# modul_procesora.net
KiCad netlist of a schematic drawn in EAGLE
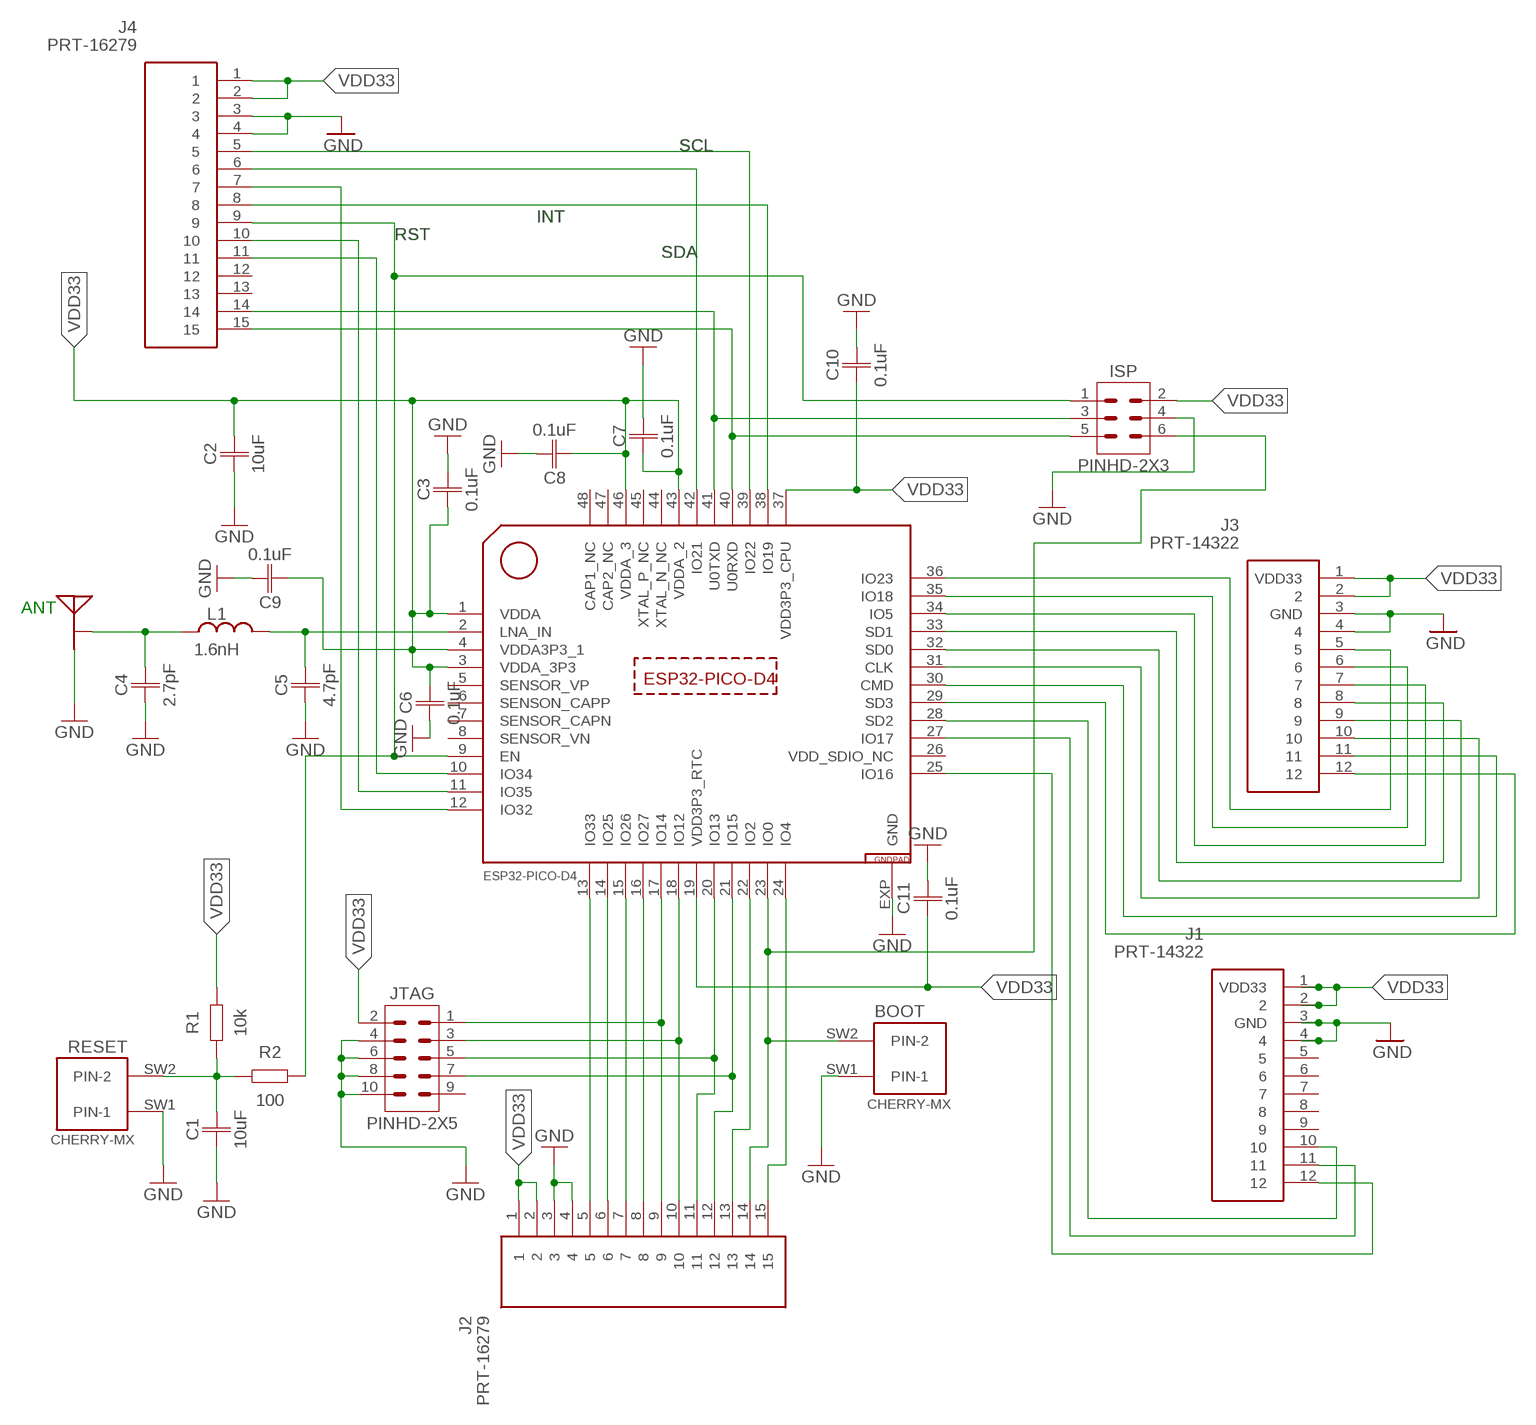
[diagram p0: schematic, sheet 1]

(export (version "E")
  (design (tool "Eeschema 10.0.6"))
  (components
    (comp (ref "ANT")
      (value "ANT")
      (footprint "eagle-import:MEANDER-ANT")
      (libsource (lib "eagle-import") (part "MEANDER-ANT"))
    )
    (comp (ref "BOOT")
      (value "BOOT")
      (footprint "eagle-import:CHERRY-MX")
      (libsource (lib "eagle-import") (part "CHERRY-MX"))
    )
    (comp (ref "C1")
      (value "10uF")
      (footprint "eagle-import:CAPC1005X60")
      (libsource (lib "eagle-import") (part "CCHIP-0402(1005-METRIC)_"))
    )
    (comp (ref "C2")
      (value "10uF")
      (footprint "eagle-import:CAPC1005X60")
      (libsource (lib "eagle-import") (part "CCHIP-0402(1005-METRIC)_"))
    )
    (comp (ref "C3")
      (value "0.1uF")
      (footprint "eagle-import:CAPC1005X60")
      (libsource (lib "eagle-import") (part "CCHIP-0402(1005-METRIC)_"))
    )
    (comp (ref "C4")
      (value "2.7pF")
      (footprint "eagle-import:CAPC1005X60")
      (libsource (lib "eagle-import") (part "CCHIP-0402(1005-METRIC)_"))
    )
    (comp (ref "C5")
      (value "4.7pF")
      (footprint "eagle-import:CAPC1005X60")
      (libsource (lib "eagle-import") (part "CCHIP-0402(1005-METRIC)_"))
    )
    (comp (ref "C6")
      (value "0.1uF")
      (footprint "eagle-import:CAPC1005X60")
      (libsource (lib "eagle-import") (part "CCHIP-0402(1005-METRIC)_"))
    )
    (comp (ref "C7")
      (value "0.1uF")
      (footprint "eagle-import:CAPC1005X60")
      (libsource (lib "eagle-import") (part "CCHIP-0402(1005-METRIC)_"))
    )
    (comp (ref "C8")
      (value "0.1uF")
      (footprint "eagle-import:CAPC1005X60")
      (libsource (lib "eagle-import") (part "CCHIP-0402(1005-METRIC)_"))
    )
    (comp (ref "C9")
      (value "0.1uF")
      (footprint "eagle-import:CAPC1005X60")
      (libsource (lib "eagle-import") (part "CCHIP-0402(1005-METRIC)_"))
    )
    (comp (ref "C10")
      (value "0.1uF")
      (footprint "eagle-import:CAPC1005X60")
      (libsource (lib "eagle-import") (part "CCHIP-0402(1005-METRIC)_"))
    )
    (comp (ref "C11")
      (value "0.1uF")
      (footprint "eagle-import:CAPC1005X60")
      (libsource (lib "eagle-import") (part "CCHIP-0402(1005-METRIC)_"))
    )
    (comp (ref "ISP")
      (value "PINHD-2X3")
      (footprint "eagle-import:2X03")
      (libsource (lib "eagle-import") (part "PINHD-2X3"))
    )
    (comp (ref "J1")
      (value "PRT-14322")
      (footprint "eagle-import:RHDR12W87P0X254_1X12_3103X250X")
      (fields (field (name "MOUSER_PART_NUMBER") "474-PRT-14322"))
      (libsource (lib "eagle-import") (part "PRT-14322"))
    )
    (comp (ref "J2")
      (value "PRT-16279")
      (footprint "eagle-import:PRT16279")
      (fields (field (name "MOUSER_PART_NUMBER") "474-PRT-16279"))
      (libsource (lib "eagle-import") (part "PRT-16279"))
    )
    (comp (ref "J3")
      (value "PRT-14322")
      (footprint "eagle-import:RHDR12W87P0X254_1X12_3103X250X")
      (fields (field (name "MOUSER_PART_NUMBER") "474-PRT-14322"))
      (libsource (lib "eagle-import") (part "PRT-14322"))
    )
    (comp (ref "J4")
      (value "PRT-16279")
      (footprint "eagle-import:PRT16279")
      (fields (field (name "MOUSER_PART_NUMBER") "474-PRT-16279"))
      (libsource (lib "eagle-import") (part "PRT-16279"))
    )
    (comp (ref "JTAG")
      (value "PINHD-2X5")
      (footprint "eagle-import:2X05")
      (libsource (lib "eagle-import") (part "PINHD-2X5"))
    )
    (comp (ref "L1")
      (value "1.6nH")
      (footprint "eagle-import:INDC1006X60N")
      (libsource (lib "eagle-import") (part "INDUCTORCHIP-0402(1006-METRIC)_"))
    )
    (comp (ref "R1")
      (value "10k")
      (footprint "eagle-import:RESC1005X40")
      (libsource (lib "eagle-import") (part "RCHIP-0402(1005-METRIC)_"))
    )
    (comp (ref "R2")
      (value "100")
      (footprint "eagle-import:RESC1005X40")
      (libsource (lib "eagle-import") (part "RCHIP-0402(1005-METRIC)_"))
    )
    (comp (ref "RESET")
      (value "CHERRY-MX")
      (footprint "eagle-import:CHERRY-MX")
      (libsource (lib "eagle-import") (part "CHERRY-MX"))
    )
    (comp (ref "U$1")
      (value "ESP32-PICO-D4")
      (footprint "eagle-import:QFN48")
      (libsource (lib "eagle-import") (part "ESP32-PICO-D4"))
    )
  )
  (nets
    (net (code "1") (name "/INT") (class "Default")
      (node (ref "J4") (pin "8") (pinfunction "8_8") (pintype "bidirectional"))
      (node (ref "U$1") (pin "38") (pinfunction "IO19_38") (pintype "bidirectional"))
    )
    (net (code "2") (name "/RST") (class "Default")
      (node (ref "ISP") (pin "1") (pinfunction "1_1") (pintype "passive"))
      (node (ref "J4") (pin "9") (pinfunction "9_9") (pintype "bidirectional"))
      (node (ref "R2") (pin "2") (pinfunction "2_2") (pintype "passive"))
      (node (ref "U$1") (pin "9") (pinfunction "EN_9") (pintype "input"))
    )
    (net (code "3") (name "/SCL") (class "Default")
      (node (ref "J4") (pin "5") (pinfunction "5_5") (pintype "bidirectional"))
      (node (ref "U$1") (pin "39") (pinfunction "IO22_39") (pintype "bidirectional"))
    )
    (net (code "4") (name "/SDA") (class "Default")
      (node (ref "J4") (pin "6") (pinfunction "6_6") (pintype "bidirectional"))
      (node (ref "U$1") (pin "42") (pinfunction "IO21_42") (pintype "bidirectional"))
    )
    (net (code "5") (name "/VDD_SDIO_NC") (class "Default")
      (node (ref "U$1") (pin "26") (pinfunction "VDD_SDIO_NC_26") (pintype "power_in"))
    )
    (net (code "6") (name "GND") (class "Default")
      (node (ref "ANT") (pin "FEED") (pinfunction "FEED_FEED") (pintype "bidirectional"))
      (node (ref "BOOT") (pin "SW1") (pinfunction "PIN-1_SW1") (pintype "bidirectional"))
      (node (ref "C1") (pin "1") (pinfunction "1_1") (pintype "passive"))
      (node (ref "C10") (pin "2") (pinfunction "2_2") (pintype "passive"))
      (node (ref "C11") (pin "2") (pinfunction "2_2") (pintype "passive"))
      (node (ref "C2") (pin "1") (pinfunction "1_1") (pintype "passive"))
      (node (ref "C3") (pin "2") (pinfunction "2_2") (pintype "passive"))
      (node (ref "C4") (pin "1") (pinfunction "1_1") (pintype "passive"))
      (node (ref "C5") (pin "1") (pinfunction "1_1") (pintype "passive"))
      (node (ref "C6") (pin "1") (pinfunction "1_1") (pintype "passive"))
      (node (ref "C7") (pin "2") (pinfunction "2_2") (pintype "passive"))
      (node (ref "C8") (pin "2") (pinfunction "2_2") (pintype "passive"))
      (node (ref "C9") (pin "2") (pinfunction "2_2") (pintype "passive"))
      (node (ref "ISP") (pin "4") (pinfunction "4_4") (pintype "passive"))
      (node (ref "J1") (pin "3") (pinfunction "GND_3") (pintype "bidirectional"))
      (node (ref "J1") (pin "4") (pinfunction "4_4") (pintype "bidirectional"))
      (node (ref "J2") (pin "3") (pinfunction "3_3") (pintype "bidirectional"))
      (node (ref "J2") (pin "4") (pinfunction "4_4") (pintype "bidirectional"))
      (node (ref "J3") (pin "3") (pinfunction "GND_3") (pintype "bidirectional"))
      (node (ref "J3") (pin "4") (pinfunction "4_4") (pintype "bidirectional"))
      (node (ref "J4") (pin "3") (pinfunction "3_3") (pintype "bidirectional"))
      (node (ref "J4") (pin "4") (pinfunction "4_4") (pintype "bidirectional"))
      (node (ref "JTAG") (pin "10") (pinfunction "10_10") (pintype "passive"))
      (node (ref "JTAG") (pin "4") (pinfunction "4_4") (pintype "passive"))
      (node (ref "JTAG") (pin "6") (pinfunction "6_6") (pintype "passive"))
      (node (ref "JTAG") (pin "8") (pinfunction "8_8") (pintype "passive"))
      (node (ref "RESET") (pin "SW1") (pinfunction "PIN-1_SW1") (pintype "bidirectional"))
      (node (ref "U$1") (pin "EXP") (pinfunction "GND_EXP") (pintype "power_in"))
    )
    (net (code "7") (name "Net-(ANT-PadGND)") (class "Default")
      (node (ref "ANT") (pin "GND") (pinfunction "GND_GND") (pintype "bidirectional"))
      (node (ref "C4") (pin "2") (pinfunction "2_2") (pintype "passive"))
      (node (ref "L1") (pin "1") (pinfunction "1_1") (pintype "passive"))
    )
    (net (code "8") (name "Net-(BOOT-PIN-2)") (class "Default")
      (node (ref "BOOT") (pin "SW2") (pinfunction "PIN-2_SW2") (pintype "bidirectional"))
      (node (ref "ISP") (pin "6") (pinfunction "6_6") (pintype "passive"))
      (node (ref "J2") (pin "14") (pinfunction "14_14") (pintype "bidirectional"))
      (node (ref "U$1") (pin "23") (pinfunction "IO0_23") (pintype "bidirectional"))
    )
    (net (code "9") (name "Net-(RESET-PIN-2)") (class "Default")
      (node (ref "C1") (pin "2") (pinfunction "2_2") (pintype "passive"))
      (node (ref "R1") (pin "1") (pinfunction "1_1") (pintype "passive"))
      (node (ref "R2") (pin "1") (pinfunction "1_1") (pintype "passive"))
      (node (ref "RESET") (pin "SW2") (pinfunction "PIN-2_SW2") (pintype "bidirectional"))
    )
    (net (code "10") (name "Net-(U$1-CLK)") (class "Default")
      (node (ref "J3") (pin "10") (pinfunction "10_10") (pintype "bidirectional"))
      (node (ref "U$1") (pin "31") (pinfunction "CLK_31") (pintype "bidirectional"))
    )
    (net (code "11") (name "Net-(U$1-CMD)") (class "Default")
      (node (ref "J3") (pin "11") (pinfunction "11_11") (pintype "bidirectional"))
      (node (ref "U$1") (pin "30") (pinfunction "CMD_30") (pintype "bidirectional"))
    )
    (net (code "12") (name "Net-(U$1-IO2)") (class "Default")
      (node (ref "J2") (pin "13") (pinfunction "13_13") (pintype "bidirectional"))
      (node (ref "U$1") (pin "22") (pinfunction "IO2_22") (pintype "bidirectional"))
    )
    (net (code "13") (name "Net-(U$1-IO4)") (class "Default")
      (node (ref "J2") (pin "15") (pinfunction "15_15") (pintype "bidirectional"))
      (node (ref "U$1") (pin "24") (pinfunction "IO4_24") (pintype "bidirectional"))
    )
    (net (code "14") (name "Net-(U$1-IO5)") (class "Default")
      (node (ref "J3") (pin "7") (pinfunction "7_7") (pintype "bidirectional"))
      (node (ref "U$1") (pin "34") (pinfunction "IO5_34") (pintype "bidirectional"))
    )
    (net (code "15") (name "Net-(U$1-IO12)") (class "Default")
      (node (ref "J2") (pin "10") (pinfunction "10_10") (pintype "bidirectional"))
      (node (ref "JTAG") (pin "3") (pinfunction "3_3") (pintype "passive"))
      (node (ref "U$1") (pin "18") (pinfunction "IO12_18") (pintype "bidirectional"))
    )
    (net (code "16") (name "Net-(U$1-IO13)") (class "Default")
      (node (ref "J2") (pin "11") (pinfunction "11_11") (pintype "bidirectional"))
      (node (ref "JTAG") (pin "5") (pinfunction "5_5") (pintype "passive"))
      (node (ref "U$1") (pin "20") (pinfunction "IO13_20") (pintype "bidirectional"))
    )
    (net (code "17") (name "Net-(U$1-IO14)") (class "Default")
      (node (ref "J2") (pin "9") (pinfunction "9_9") (pintype "bidirectional"))
      (node (ref "JTAG") (pin "1") (pinfunction "1_1") (pintype "passive"))
      (node (ref "U$1") (pin "17") (pinfunction "IO14_17") (pintype "bidirectional"))
    )
    (net (code "18") (name "Net-(U$1-IO15)") (class "Default")
      (node (ref "J2") (pin "12") (pinfunction "12_12") (pintype "bidirectional"))
      (node (ref "JTAG") (pin "7") (pinfunction "7_7") (pintype "passive"))
      (node (ref "U$1") (pin "21") (pinfunction "IO15_21") (pintype "bidirectional"))
    )
    (net (code "19") (name "Net-(U$1-IO16)") (class "Default")
      (node (ref "J1") (pin "12") (pinfunction "12_12") (pintype "bidirectional"))
      (node (ref "U$1") (pin "25") (pinfunction "IO16_25") (pintype "bidirectional"))
    )
    (net (code "20") (name "Net-(U$1-IO17)") (class "Default")
      (node (ref "J1") (pin "11") (pinfunction "11_11") (pintype "bidirectional"))
      (node (ref "U$1") (pin "27") (pinfunction "IO17_27") (pintype "bidirectional"))
    )
    (net (code "21") (name "Net-(U$1-IO18)") (class "Default")
      (node (ref "J3") (pin "6") (pinfunction "6_6") (pintype "bidirectional"))
      (node (ref "U$1") (pin "35") (pinfunction "IO18_35") (pintype "bidirectional"))
    )
    (net (code "22") (name "Net-(U$1-IO23)") (class "Default")
      (node (ref "J3") (pin "5") (pinfunction "5_5") (pintype "bidirectional"))
      (node (ref "U$1") (pin "36") (pinfunction "IO23_36") (pintype "bidirectional"))
    )
    (net (code "23") (name "Net-(U$1-IO25)") (class "Default")
      (node (ref "J2") (pin "6") (pinfunction "6_6") (pintype "bidirectional"))
      (node (ref "U$1") (pin "14") (pinfunction "IO25_14") (pintype "bidirectional"))
    )
    (net (code "24") (name "Net-(U$1-IO26)") (class "Default")
      (node (ref "J2") (pin "7") (pinfunction "7_7") (pintype "bidirectional"))
      (node (ref "U$1") (pin "15") (pinfunction "IO26_15") (pintype "bidirectional"))
    )
    (net (code "25") (name "Net-(U$1-IO27)") (class "Default")
      (node (ref "J2") (pin "8") (pinfunction "8_8") (pintype "bidirectional"))
      (node (ref "U$1") (pin "16") (pinfunction "IO27_16") (pintype "bidirectional"))
    )
    (net (code "26") (name "Net-(U$1-IO32)") (class "Default")
      (node (ref "J4") (pin "7") (pinfunction "7_7") (pintype "bidirectional"))
      (node (ref "U$1") (pin "12") (pinfunction "IO32_12") (pintype "bidirectional"))
    )
    (net (code "27") (name "Net-(U$1-IO33)") (class "Default")
      (node (ref "J2") (pin "5") (pinfunction "5_5") (pintype "bidirectional"))
      (node (ref "U$1") (pin "13") (pinfunction "IO33_13") (pintype "bidirectional"))
    )
    (net (code "28") (name "Net-(U$1-IO34)") (class "Default")
      (node (ref "J4") (pin "11") (pinfunction "11_11") (pintype "bidirectional"))
      (node (ref "U$1") (pin "10") (pinfunction "IO34_10") (pintype "bidirectional"))
    )
    (net (code "29") (name "Net-(U$1-IO35)") (class "Default")
      (node (ref "J4") (pin "10") (pinfunction "10_10") (pintype "bidirectional"))
      (node (ref "U$1") (pin "11") (pinfunction "IO35_11") (pintype "bidirectional"))
    )
    (net (code "30") (name "Net-(U$1-LNA_IN)") (class "Default")
      (node (ref "C5") (pin "2") (pinfunction "2_2") (pintype "passive"))
      (node (ref "L1") (pin "2") (pinfunction "2_2") (pintype "passive"))
      (node (ref "U$1") (pin "2") (pinfunction "LNA_IN_2") (pintype "bidirectional"))
    )
    (net (code "31") (name "Net-(U$1-SD0)") (class "Default")
      (node (ref "J3") (pin "9") (pinfunction "9_9") (pintype "bidirectional"))
      (node (ref "U$1") (pin "32") (pinfunction "SD0_32") (pintype "bidirectional"))
    )
    (net (code "32") (name "Net-(U$1-SD1)") (class "Default")
      (node (ref "J3") (pin "8") (pinfunction "8_8") (pintype "bidirectional"))
      (node (ref "U$1") (pin "33") (pinfunction "SD1_33") (pintype "bidirectional"))
    )
    (net (code "33") (name "Net-(U$1-SD2)") (class "Default")
      (node (ref "J1") (pin "10") (pinfunction "10_10") (pintype "bidirectional"))
      (node (ref "U$1") (pin "28") (pinfunction "SD2_28") (pintype "bidirectional"))
    )
    (net (code "34") (name "Net-(U$1-SD3)") (class "Default")
      (node (ref "J3") (pin "12") (pinfunction "12_12") (pintype "bidirectional"))
      (node (ref "U$1") (pin "29") (pinfunction "SD3_29") (pintype "bidirectional"))
    )
    (net (code "35") (name "Net-(U$1-U0RXD)") (class "Default")
      (node (ref "ISP") (pin "5") (pinfunction "5_5") (pintype "passive"))
      (node (ref "J4") (pin "15") (pinfunction "15_15") (pintype "bidirectional"))
      (node (ref "U$1") (pin "40") (pinfunction "U0RXD_40") (pintype "bidirectional"))
    )
    (net (code "36") (name "Net-(U$1-U0TXD)") (class "Default")
      (node (ref "ISP") (pin "3") (pinfunction "3_3") (pintype "passive"))
      (node (ref "J4") (pin "14") (pinfunction "14_14") (pintype "bidirectional"))
      (node (ref "U$1") (pin "41") (pinfunction "U0TXD_41") (pintype "bidirectional"))
    )
    (net (code "37") (name "VDD33") (class "Default")
      (node (ref "C10") (pin "1") (pinfunction "1_1") (pintype "passive"))
      (node (ref "C11") (pin "1") (pinfunction "1_1") (pintype "passive"))
      (node (ref "C2") (pin "2") (pinfunction "2_2") (pintype "passive"))
      (node (ref "C3") (pin "1") (pinfunction "1_1") (pintype "passive"))
      (node (ref "C6") (pin "2") (pinfunction "2_2") (pintype "passive"))
      (node (ref "C7") (pin "1") (pinfunction "1_1") (pintype "passive"))
      (node (ref "C8") (pin "1") (pinfunction "1_1") (pintype "passive"))
      (node (ref "C9") (pin "1") (pinfunction "1_1") (pintype "passive"))
      (node (ref "ISP") (pin "2") (pinfunction "2_2") (pintype "passive"))
      (node (ref "J1") (pin "1") (pinfunction "VDD33_1") (pintype "bidirectional"))
      (node (ref "J1") (pin "2") (pinfunction "2_2") (pintype "bidirectional"))
      (node (ref "J2") (pin "1") (pinfunction "1_1") (pintype "bidirectional"))
      (node (ref "J2") (pin "2") (pinfunction "2_2") (pintype "bidirectional"))
      (node (ref "J3") (pin "1") (pinfunction "VDD33_1") (pintype "bidirectional"))
      (node (ref "J3") (pin "2") (pinfunction "2_2") (pintype "bidirectional"))
      (node (ref "J4") (pin "1") (pinfunction "1_1") (pintype "bidirectional"))
      (node (ref "J4") (pin "2") (pinfunction "2_2") (pintype "bidirectional"))
      (node (ref "JTAG") (pin "2") (pinfunction "2_2") (pintype "passive"))
      (node (ref "R1") (pin "2") (pinfunction "2_2") (pintype "passive"))
      (node (ref "U$1") (pin "1") (pinfunction "VDDA_1") (pintype "power_in"))
      (node (ref "U$1") (pin "19") (pinfunction "VDD3P3_RTC_19") (pintype "power_in"))
      (node (ref "U$1") (pin "3") (pinfunction "VDDA_3P3_3") (pintype "power_in"))
      (node (ref "U$1") (pin "37") (pinfunction "VDD3P3_CPU_37") (pintype "power_in"))
      (node (ref "U$1") (pin "4") (pinfunction "VDDA3P3_1_4") (pintype "power_in"))
      (node (ref "U$1") (pin "43") (pinfunction "VDDA_2_43") (pintype "power_in"))
      (node (ref "U$1") (pin "46") (pinfunction "VDDA_3_46") (pintype "power_in"))
    )
    (net (code "38") (name "unconnected-(J1-Pad5)") (class "Default")
      (node (ref "J1") (pin "5") (pinfunction "5_5") (pintype "bidirectional"))
    )
    (net (code "39") (name "unconnected-(J1-Pad6)") (class "Default")
      (node (ref "J1") (pin "6") (pinfunction "6_6") (pintype "bidirectional"))
    )
    (net (code "40") (name "unconnected-(J1-Pad7)") (class "Default")
      (node (ref "J1") (pin "7") (pinfunction "7_7") (pintype "bidirectional"))
    )
    (net (code "41") (name "unconnected-(J1-Pad8)") (class "Default")
      (node (ref "J1") (pin "8") (pinfunction "8_8") (pintype "bidirectional"))
    )
    (net (code "42") (name "unconnected-(J1-Pad9)") (class "Default")
      (node (ref "J1") (pin "9") (pinfunction "9_9") (pintype "bidirectional"))
    )
    (net (code "43") (name "unconnected-(J4-Pad12)") (class "Default")
      (node (ref "J4") (pin "12") (pinfunction "12_12") (pintype "bidirectional"))
    )
    (net (code "44") (name "unconnected-(J4-Pad13)") (class "Default")
      (node (ref "J4") (pin "13") (pinfunction "13_13") (pintype "bidirectional"))
    )
    (net (code "45") (name "unconnected-(JTAG-Pad9)") (class "Default")
      (node (ref "JTAG") (pin "9") (pinfunction "9_9") (pintype "passive"))
    )
    (net (code "46") (name "unconnected-(U$1-CAP1_NC-Pad48)") (class "Default")
      (node (ref "U$1") (pin "48") (pinfunction "CAP1_NC_48") (pintype "bidirectional"))
    )
    (net (code "47") (name "unconnected-(U$1-CAP2_NC-Pad47)") (class "Default")
      (node (ref "U$1") (pin "47") (pinfunction "CAP2_NC_47") (pintype "bidirectional"))
    )
    (net (code "48") (name "unconnected-(U$1-SENSON_CAPP-Pad6)") (class "Default")
      (node (ref "U$1") (pin "6") (pinfunction "SENSON_CAPP_6") (pintype "input"))
    )
    (net (code "49") (name "unconnected-(U$1-SENSOR_CAPN-Pad7)") (class "Default")
      (node (ref "U$1") (pin "7") (pinfunction "SENSOR_CAPN_7") (pintype "input"))
    )
    (net (code "50") (name "unconnected-(U$1-SENSOR_VN-Pad8)") (class "Default")
      (node (ref "U$1") (pin "8") (pinfunction "SENSOR_VN_8") (pintype "input"))
    )
    (net (code "51") (name "unconnected-(U$1-SENSOR_VP-Pad5)") (class "Default")
      (node (ref "U$1") (pin "5") (pinfunction "SENSOR_VP_5") (pintype "input"))
    )
    (net (code "52") (name "unconnected-(U$1-XTAL_N_NC-Pad44)") (class "Default")
      (node (ref "U$1") (pin "44") (pinfunction "XTAL_N_NC_44") (pintype "bidirectional"))
    )
    (net (code "53") (name "unconnected-(U$1-XTAL_P_NC-Pad45)") (class "Default")
      (node (ref "U$1") (pin "45") (pinfunction "XTAL_P_NC_45") (pintype "bidirectional"))
    )
  )
)
